# schema_v4_0.net
KiCad netlist of a schematic drawn in EAGLE
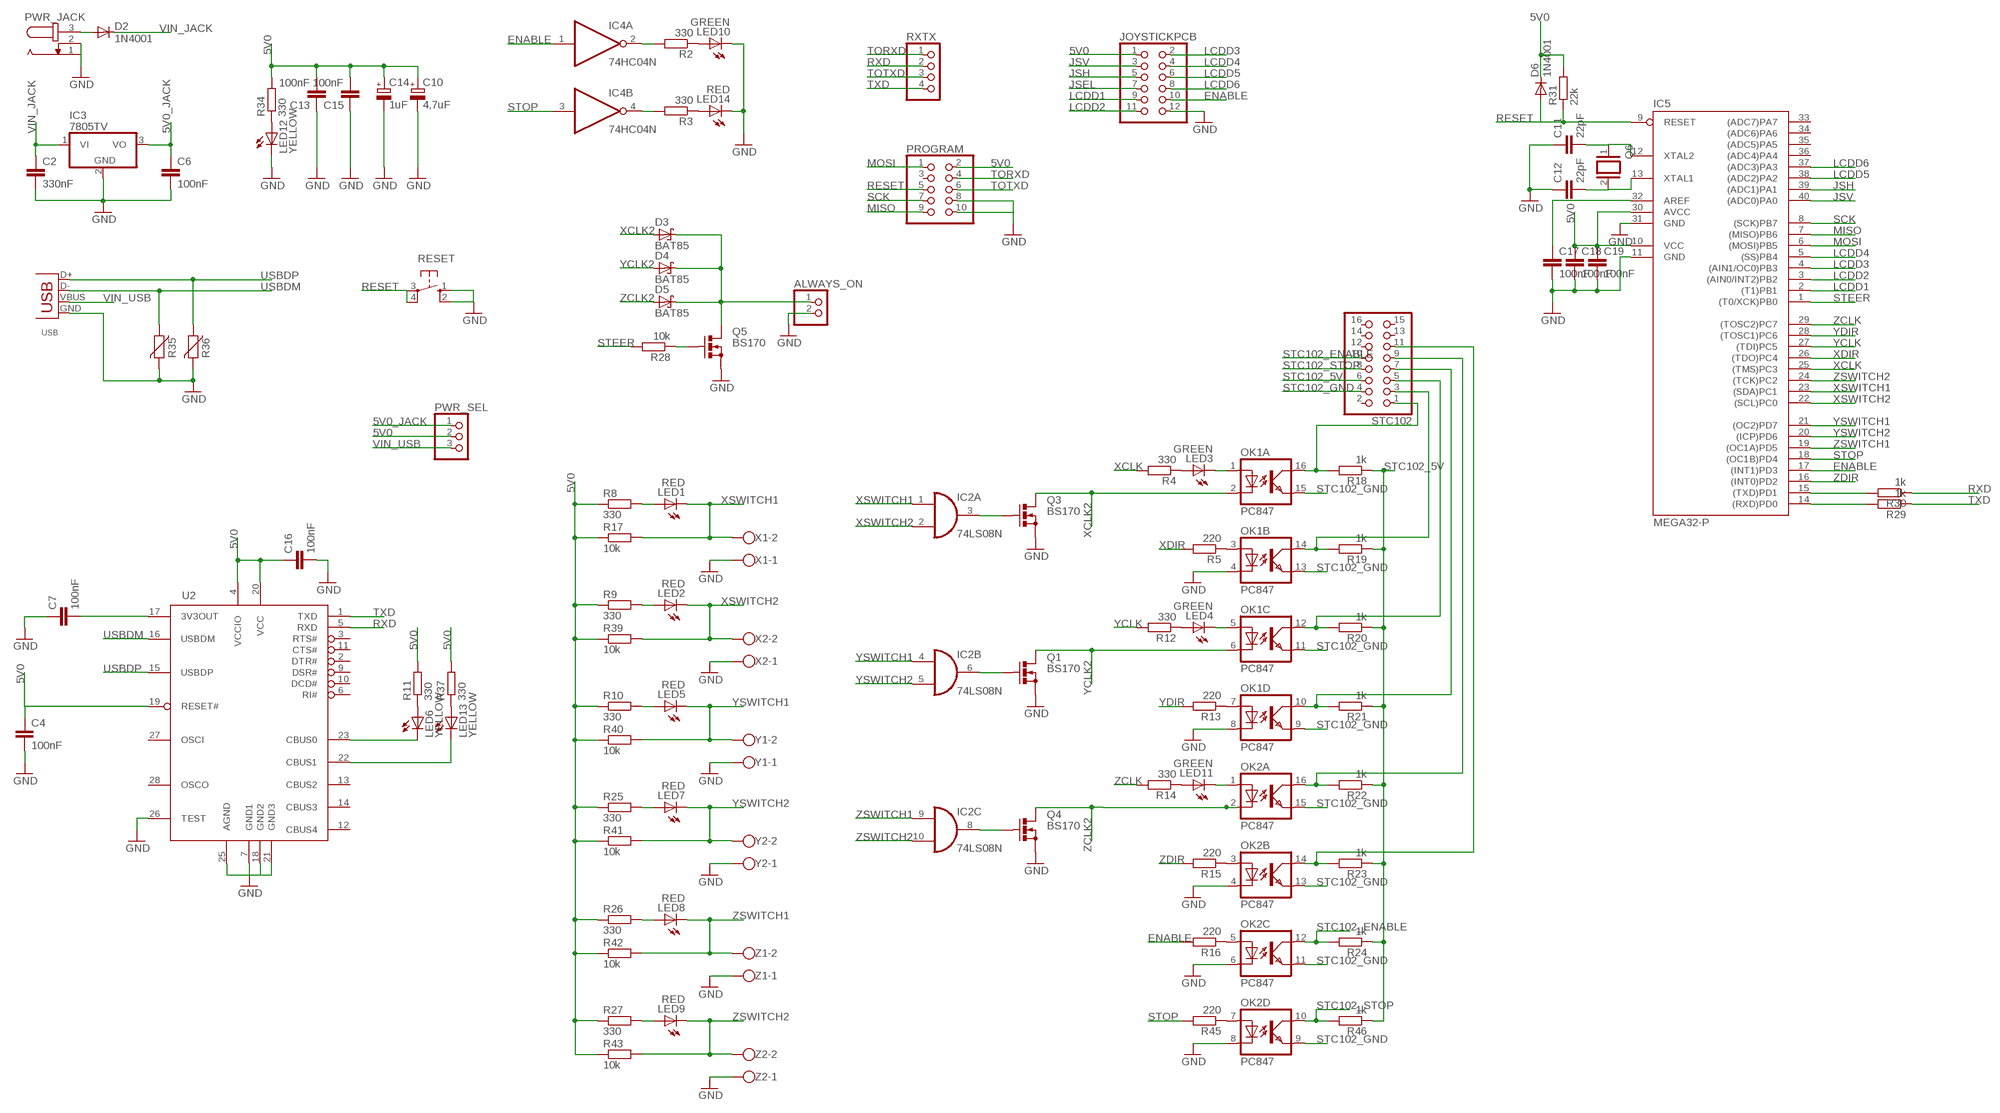
[diagram p0: schematic, sheet 1]

(export (version "E")
  (design (tool "Eeschema 10.0.6"))
  (components
    (comp (ref "ALWAYS_ON")
      (value "PINHD-1X2")
      (footprint "eagle-import:1X02")
      (libsource (lib "eagle-import") (part "PINHD-1X2"))
    )
    (comp (ref "C2")
      (value "330nF")
      (footprint "eagle-import:C025-025X050")
      (libsource (lib "eagle-import") (part "C-EU025-025X050"))
    )
    (comp (ref "C4")
      (value "100nF")
      (footprint "eagle-import:C0805K")
      (libsource (lib "eagle-import") (part "C-EUC0805K"))
    )
    (comp (ref "C6")
      (value "100nF")
      (footprint "eagle-import:C025-025X050")
      (libsource (lib "eagle-import") (part "C-EU025-025X050"))
    )
    (comp (ref "C7")
      (value "100nF")
      (footprint "eagle-import:C0805K")
      (libsource (lib "eagle-import") (part "C-EUC0805K"))
    )
    (comp (ref "C10")
      (value "4,7uF")
      (footprint "eagle-import:E2,5-5")
      (libsource (lib "eagle-import") (part "CPOL-EUE2.5-5"))
    )
    (comp (ref "C11")
      (value "22pF")
      (footprint "eagle-import:C0805K")
      (libsource (lib "eagle-import") (part "C-EUC0805K"))
    )
    (comp (ref "C12")
      (value "22pF")
      (footprint "eagle-import:C0805K")
      (libsource (lib "eagle-import") (part "C-EUC0805K"))
    )
    (comp (ref "C13")
      (value "100nF")
      (footprint "eagle-import:C025-025X050")
      (libsource (lib "eagle-import") (part "C-EU025-025X050"))
    )
    (comp (ref "C14")
      (value "1uF")
      (footprint "eagle-import:E2,5-5")
      (libsource (lib "eagle-import") (part "CPOL-EUE2.5-5"))
    )
    (comp (ref "C15")
      (value "100nF")
      (footprint "eagle-import:C025-025X050")
      (libsource (lib "eagle-import") (part "C-EU025-025X050"))
    )
    (comp (ref "C16")
      (value "100nF")
      (footprint "eagle-import:C0805K")
      (libsource (lib "eagle-import") (part "C-EUC0805K"))
    )
    (comp (ref "C17")
      (value "100nF")
      (footprint "eagle-import:C0805K")
      (libsource (lib "eagle-import") (part "C-EUC0805K"))
    )
    (comp (ref "C18")
      (value "100nF")
      (footprint "eagle-import:C0805K")
      (libsource (lib "eagle-import") (part "C-EUC0805K"))
    )
    (comp (ref "C19")
      (value "100nF")
      (footprint "eagle-import:C0805K")
      (libsource (lib "eagle-import") (part "C-EUC0805K"))
    )
    (comp (ref "D2")
      (value "1N4001")
      (footprint "eagle-import:DO41-10")
      (libsource (lib "eagle-import") (part "1N4004"))
    )
    (comp (ref "D3")
      (value "BAT85")
      (footprint "eagle-import:DO35-10")
      (libsource (lib "eagle-import") (part "BAT42"))
    )
    (comp (ref "D4")
      (value "BAT85")
      (footprint "eagle-import:DO35-10")
      (libsource (lib "eagle-import") (part "BAT42"))
    )
    (comp (ref "D5")
      (value "BAT85")
      (footprint "eagle-import:DO35-10")
      (libsource (lib "eagle-import") (part "BAT42"))
    )
    (comp (ref "D6")
      (value "1N4001")
      (footprint "eagle-import:DO41-10")
      (libsource (lib "eagle-import") (part "1N4004"))
    )
    (comp (ref "IC2")
      (value "74LS08N")
      (footprint "eagle-import:DIL14")
      (libsource (lib "eagle-import") (part "7408NLS"))
    )
    (comp (ref "IC3")
      (value "7805TV")
      (footprint "eagle-import:TO220V")
      (libsource (lib "eagle-import") (part "78TV05"))
    )
    (comp (ref "IC4")
      (value "74HC04N")
      (footprint "eagle-import:DIL14")
      (libsource (lib "eagle-import") (part "7404NHC"))
    )
    (comp (ref "IC5")
      (value "MEGA32-P")
      (footprint "eagle-import:DIL40")
      (fields (field (name "MPN") "ATMEGA32-16PU"))
      (libsource (lib "eagle-import") (part "MEGA32-P"))
    )
    (comp (ref "JOYSTICKPCB")
      (value "PINHD-2X6")
      (footprint "eagle-import:2X06")
      (libsource (lib "eagle-import") (part "PINHD-2X6"))
    )
    (comp (ref "LED1")
      (value "RED")
      (footprint "eagle-import:LED3MM")
      (libsource (lib "eagle-import") (part "LED3MM"))
    )
    (comp (ref "LED2")
      (value "RED")
      (footprint "eagle-import:LED3MM")
      (libsource (lib "eagle-import") (part "LED3MM"))
    )
    (comp (ref "LED3")
      (value "GREEN")
      (footprint "eagle-import:LED3MM")
      (libsource (lib "eagle-import") (part "LED3MM"))
    )
    (comp (ref "LED4")
      (value "GREEN")
      (footprint "eagle-import:LED3MM")
      (libsource (lib "eagle-import") (part "LED3MM"))
    )
    (comp (ref "LED5")
      (value "RED")
      (footprint "eagle-import:LED3MM")
      (libsource (lib "eagle-import") (part "LED3MM"))
    )
    (comp (ref "LED6")
      (value "YELLOW")
      (footprint "eagle-import:LED3MM")
      (libsource (lib "eagle-import") (part "LED3MM"))
    )
    (comp (ref "LED7")
      (value "RED")
      (footprint "eagle-import:LED3MM")
      (libsource (lib "eagle-import") (part "LED3MM"))
    )
    (comp (ref "LED8")
      (value "RED")
      (footprint "eagle-import:LED3MM")
      (libsource (lib "eagle-import") (part "LED3MM"))
    )
    (comp (ref "LED9")
      (value "RED")
      (footprint "eagle-import:LED3MM")
      (libsource (lib "eagle-import") (part "LED3MM"))
    )
    (comp (ref "LED10")
      (value "GREEN")
      (footprint "eagle-import:LED3MM")
      (libsource (lib "eagle-import") (part "LED3MM"))
    )
    (comp (ref "LED11")
      (value "GREEN")
      (footprint "eagle-import:LED3MM")
      (libsource (lib "eagle-import") (part "LED3MM"))
    )
    (comp (ref "LED12")
      (value "YELLOW")
      (footprint "eagle-import:LED3MM")
      (libsource (lib "eagle-import") (part "LED3MM"))
    )
    (comp (ref "LED13")
      (value "YELLOW")
      (footprint "eagle-import:LED3MM")
      (libsource (lib "eagle-import") (part "LED3MM"))
    )
    (comp (ref "LED14")
      (value "RED")
      (footprint "eagle-import:LED3MM")
      (libsource (lib "eagle-import") (part "LED3MM"))
    )
    (comp (ref "OK1")
      (value "PC847")
      (footprint "eagle-import:DIL16")
      (libsource (lib "eagle-import") (part "PC847"))
    )
    (comp (ref "OK2")
      (value "PC847")
      (footprint "eagle-import:DIL16")
      (libsource (lib "eagle-import") (part "PC847"))
    )
    (comp (ref "PROGRAM")
      (value "PINHD-2X5")
      (footprint "eagle-import:2X05")
      (libsource (lib "eagle-import") (part "PINHD-2X5"))
    )
    (comp (ref "PWR_JACK")
      (value "JACK-PLUG0")
      (footprint "eagle-import:SPC4077")
      (libsource (lib "eagle-import") (part "JACK-PLUG0"))
    )
    (comp (ref "PWR_SEL")
      (value "PINHD-1X3")
      (footprint "eagle-import:1X03")
      (libsource (lib "eagle-import") (part "PINHD-1X3"))
    )
    (comp (ref "Q1")
      (value "BS170")
      (footprint "eagle-import:SOT54E")
      (libsource (lib "eagle-import") (part "BS170"))
    )
    (comp (ref "Q3")
      (value "BS170")
      (footprint "eagle-import:SOT54E")
      (libsource (lib "eagle-import") (part "BS170"))
    )
    (comp (ref "Q4")
      (value "BS170")
      (footprint "eagle-import:SOT54E")
      (libsource (lib "eagle-import") (part "BS170"))
    )
    (comp (ref "Q5")
      (value "BS170")
      (footprint "eagle-import:SOT54E")
      (libsource (lib "eagle-import") (part "BS170"))
    )
    (comp (ref "Q6")
      (value "XTAL/S")
      (footprint "eagle-import:QS")
      (libsource (lib "eagle-import") (part "XTAL/S"))
    )
    (comp (ref "R2")
      (value "330")
      (footprint "eagle-import:0207_10")
      (libsource (lib "eagle-import") (part "R-EU_0207/10"))
    )
    (comp (ref "R3")
      (value "330")
      (footprint "eagle-import:0207_10")
      (libsource (lib "eagle-import") (part "R-EU_0207/10"))
    )
    (comp (ref "R4")
      (value "330")
      (footprint "eagle-import:0207_10")
      (libsource (lib "eagle-import") (part "R-EU_0207/10"))
    )
    (comp (ref "R5")
      (value "220")
      (footprint "eagle-import:0207_10")
      (libsource (lib "eagle-import") (part "R-EU_0207/10"))
    )
    (comp (ref "R8")
      (value "330")
      (footprint "eagle-import:R0805")
      (libsource (lib "eagle-import") (part "R-EU_R0805"))
    )
    (comp (ref "R9")
      (value "330")
      (footprint "eagle-import:R0805")
      (libsource (lib "eagle-import") (part "R-EU_R0805"))
    )
    (comp (ref "R10")
      (value "330")
      (footprint "eagle-import:R0805")
      (libsource (lib "eagle-import") (part "R-EU_R0805"))
    )
    (comp (ref "R11")
      (value "330")
      (footprint "eagle-import:R0805")
      (libsource (lib "eagle-import") (part "R-EU_R0805"))
    )
    (comp (ref "R12")
      (value "330")
      (footprint "eagle-import:0207_10")
      (libsource (lib "eagle-import") (part "R-EU_0207/10"))
    )
    (comp (ref "R13")
      (value "220")
      (footprint "eagle-import:0207_10")
      (libsource (lib "eagle-import") (part "R-EU_0207/10"))
    )
    (comp (ref "R14")
      (value "330")
      (footprint "eagle-import:0207_10")
      (libsource (lib "eagle-import") (part "R-EU_0207/10"))
    )
    (comp (ref "R15")
      (value "220")
      (footprint "eagle-import:0207_10")
      (libsource (lib "eagle-import") (part "R-EU_0207/10"))
    )
    (comp (ref "R16")
      (value "220")
      (footprint "eagle-import:0207_10")
      (libsource (lib "eagle-import") (part "R-EU_0207/10"))
    )
    (comp (ref "R17")
      (value "10k")
      (footprint "eagle-import:0207_10")
      (libsource (lib "eagle-import") (part "R-EU_0207/10"))
    )
    (comp (ref "R18")
      (value "1k")
      (footprint "eagle-import:0207_10")
      (libsource (lib "eagle-import") (part "R-EU_0207/10"))
    )
    (comp (ref "R19")
      (value "1k")
      (footprint "eagle-import:0207_10")
      (libsource (lib "eagle-import") (part "R-EU_0207/10"))
    )
    (comp (ref "R20")
      (value "1k")
      (footprint "eagle-import:0207_10")
      (libsource (lib "eagle-import") (part "R-EU_0207/10"))
    )
    (comp (ref "R21")
      (value "1k")
      (footprint "eagle-import:0207_10")
      (libsource (lib "eagle-import") (part "R-EU_0207/10"))
    )
    (comp (ref "R22")
      (value "1k")
      (footprint "eagle-import:0207_10")
      (libsource (lib "eagle-import") (part "R-EU_0207/10"))
    )
    (comp (ref "R23")
      (value "1k")
      (footprint "eagle-import:0207_10")
      (libsource (lib "eagle-import") (part "R-EU_0207/10"))
    )
    (comp (ref "R24")
      (value "1k")
      (footprint "eagle-import:0207_10")
      (libsource (lib "eagle-import") (part "R-EU_0207/10"))
    )
    (comp (ref "R25")
      (value "330")
      (footprint "eagle-import:R0805")
      (libsource (lib "eagle-import") (part "R-EU_R0805"))
    )
    (comp (ref "R26")
      (value "330")
      (footprint "eagle-import:R0805")
      (libsource (lib "eagle-import") (part "R-EU_R0805"))
    )
    (comp (ref "R27")
      (value "330")
      (footprint "eagle-import:R0805")
      (libsource (lib "eagle-import") (part "R-EU_R0805"))
    )
    (comp (ref "R28")
      (value "10k")
      (footprint "eagle-import:0207_10")
      (libsource (lib "eagle-import") (part "R-EU_0207/10"))
    )
    (comp (ref "R29")
      (value "1k")
      (footprint "eagle-import:R0805")
      (libsource (lib "eagle-import") (part "R-EU_R0805"))
    )
    (comp (ref "R30")
      (value "1k")
      (footprint "eagle-import:R0805")
      (libsource (lib "eagle-import") (part "R-EU_R0805"))
    )
    (comp (ref "R31")
      (value "22k")
      (footprint "eagle-import:0207_10")
      (libsource (lib "eagle-import") (part "R-EU_0207/10"))
    )
    (comp (ref "R34")
      (value "330")
      (footprint "eagle-import:0207_10")
      (libsource (lib "eagle-import") (part "R-EU_0207/10"))
    )
    (comp (ref "R35")
      (value "VARISTORCN0603")
      (footprint "eagle-import:CT_CN0603")
      (libsource (lib "eagle-import") (part "VARISTORCN0603"))
    )
    (comp (ref "R36")
      (value "VARISTORCN0603")
      (footprint "eagle-import:CT_CN0603")
      (libsource (lib "eagle-import") (part "VARISTORCN0603"))
    )
    (comp (ref "R37")
      (value "330")
      (footprint "eagle-import:R0805")
      (libsource (lib "eagle-import") (part "R-EU_R0805"))
    )
    (comp (ref "R39")
      (value "10k")
      (footprint "eagle-import:0207_10")
      (libsource (lib "eagle-import") (part "R-EU_0207/10"))
    )
    (comp (ref "R40")
      (value "10k")
      (footprint "eagle-import:0207_10")
      (libsource (lib "eagle-import") (part "R-EU_0207/10"))
    )
    (comp (ref "R41")
      (value "10k")
      (footprint "eagle-import:0207_10")
      (libsource (lib "eagle-import") (part "R-EU_0207/10"))
    )
    (comp (ref "R42")
      (value "10k")
      (footprint "eagle-import:0207_10")
      (libsource (lib "eagle-import") (part "R-EU_0207/10"))
    )
    (comp (ref "R43")
      (value "10k")
      (footprint "eagle-import:0207_10")
      (libsource (lib "eagle-import") (part "R-EU_0207/10"))
    )
    (comp (ref "R45")
      (value "220")
      (footprint "eagle-import:0207_10")
      (libsource (lib "eagle-import") (part "R-EU_0207/10"))
    )
    (comp (ref "R46")
      (value "1k")
      (footprint "eagle-import:0207_10")
      (libsource (lib "eagle-import") (part "R-EU_0207/10"))
    )
    (comp (ref "RESET")
      (value "10-XX")
      (footprint "eagle-import:B3F-10XX")
      (fields (field (name "MPN") "B3F-1000"))
      (libsource (lib "eagle-import") (part "10-XX"))
    )
    (comp (ref "RXTX")
      (value "PINHD-1X4")
      (footprint "eagle-import:1X04")
      (libsource (lib "eagle-import") (part "PINHD-1X4"))
    )
    (comp (ref "STC102")
      (value "PINHD-2X8")
      (footprint "eagle-import:2X08")
      (libsource (lib "eagle-import") (part "PINHD-2X8"))
    )
    (comp (ref "U2")
      (value "FT232RL")
      (footprint "eagle-import:SSOP28DB")
      (libsource (lib "eagle-import") (part "FT232RL"))
    )
    (comp (ref "USB")
      (value "USB-B-H")
      (footprint "eagle-import:USB-B-H")
      (libsource (lib "eagle-import") (part "USB-B-H"))
    )
    (comp (ref "X1")
      (value "W237-102")
      (footprint "eagle-import:W237-102")
      (fields (field (name "MPN") "237-102"))
      (libsource (lib "eagle-import") (part "W237-102"))
    )
    (comp (ref "X2")
      (value "W237-102")
      (footprint "eagle-import:W237-102")
      (fields (field (name "MPN") "237-102"))
      (libsource (lib "eagle-import") (part "W237-102"))
    )
    (comp (ref "Y1")
      (value "W237-102")
      (footprint "eagle-import:W237-102")
      (fields (field (name "MPN") "237-102"))
      (libsource (lib "eagle-import") (part "W237-102"))
    )
    (comp (ref "Y2")
      (value "W237-102")
      (footprint "eagle-import:W237-102")
      (fields (field (name "MPN") "237-102"))
      (libsource (lib "eagle-import") (part "W237-102"))
    )
    (comp (ref "Z1")
      (value "W237-102")
      (footprint "eagle-import:W237-102")
      (fields (field (name "MPN") "237-102"))
      (libsource (lib "eagle-import") (part "W237-102"))
    )
    (comp (ref "Z2")
      (value "W237-102")
      (footprint "eagle-import:W237-102")
      (fields (field (name "MPN") "237-102"))
      (libsource (lib "eagle-import") (part "W237-102"))
    )
  )
  (nets
    (net (code "1") (name "/5V0") (class "Default")
      (node (ref "C10") (pin "+") (pinfunction "+_+") (pintype "passive"))
      (node (ref "C13") (pin "2") (pinfunction "2_2") (pintype "passive"))
      (node (ref "C14") (pin "+") (pinfunction "+_+") (pintype "passive"))
      (node (ref "C15") (pin "2") (pinfunction "2_2") (pintype "passive"))
      (node (ref "C16") (pin "1") (pinfunction "1_1") (pintype "passive"))
      (node (ref "C18") (pin "1") (pinfunction "1_1") (pintype "passive"))
      (node (ref "C19") (pin "1") (pinfunction "1_1") (pintype "passive"))
      (node (ref "C4") (pin "1") (pinfunction "1_1") (pintype "passive"))
      (node (ref "D6") (pin "C") (pinfunction "C_C") (pintype "passive"))
      (node (ref "IC5") (pin "10") (pinfunction "VCC_10") (pintype "power_in"))
      (node (ref "IC5") (pin "30") (pinfunction "AVCC_30") (pintype "power_in"))
      (node (ref "JOYSTICKPCB") (pin "1") (pinfunction "1_1") (pintype "passive"))
      (node (ref "PROGRAM") (pin "2") (pinfunction "2_2") (pintype "passive"))
      (node (ref "PWR_SEL") (pin "2") (pinfunction "2_2") (pintype "passive"))
      (node (ref "R10") (pin "1") (pinfunction "1_1") (pintype "passive"))
      (node (ref "R11") (pin "2") (pinfunction "2_2") (pintype "passive"))
      (node (ref "R17") (pin "1") (pinfunction "1_1") (pintype "passive"))
      (node (ref "R25") (pin "1") (pinfunction "1_1") (pintype "passive"))
      (node (ref "R26") (pin "1") (pinfunction "1_1") (pintype "passive"))
      (node (ref "R27") (pin "1") (pinfunction "1_1") (pintype "passive"))
      (node (ref "R31") (pin "2") (pinfunction "2_2") (pintype "passive"))
      (node (ref "R34") (pin "2") (pinfunction "2_2") (pintype "passive"))
      (node (ref "R37") (pin "2") (pinfunction "2_2") (pintype "passive"))
      (node (ref "R39") (pin "1") (pinfunction "1_1") (pintype "passive"))
      (node (ref "R40") (pin "1") (pinfunction "1_1") (pintype "passive"))
      (node (ref "R41") (pin "1") (pinfunction "1_1") (pintype "passive"))
      (node (ref "R42") (pin "1") (pinfunction "1_1") (pintype "passive"))
      (node (ref "R43") (pin "1") (pinfunction "1_1") (pintype "passive"))
      (node (ref "R8") (pin "1") (pinfunction "1_1") (pintype "passive"))
      (node (ref "R9") (pin "1") (pinfunction "1_1") (pintype "passive"))
      (node (ref "U2") (pin "19") (pinfunction "RESET#_19") (pintype "input"))
      (node (ref "U2") (pin "20") (pinfunction "VCC_20") (pintype "power_in"))
      (node (ref "U2") (pin "4") (pinfunction "VCCIO_4") (pintype "power_in"))
    )
    (net (code "2") (name "/5V0_JACK") (class "Default")
      (node (ref "C6") (pin "1") (pinfunction "1_1") (pintype "passive"))
      (node (ref "IC3") (pin "3") (pinfunction "VO_3") (pintype "passive"))
      (node (ref "PWR_SEL") (pin "1") (pinfunction "1_1") (pintype "passive"))
    )
    (net (code "3") (name "/ENABLE") (class "Default")
      (node (ref "IC4") (pin "1") (pinfunction "I_1") (pintype "input"))
      (node (ref "IC5") (pin "17") (pinfunction "(INT1)PD3_17") (pintype "bidirectional"))
      (node (ref "JOYSTICKPCB") (pin "10") (pinfunction "10_10") (pintype "passive"))
      (node (ref "R16") (pin "2") (pinfunction "2_2") (pintype "passive"))
    )
    (net (code "4") (name "/JSEL") (class "Default")
      (node (ref "JOYSTICKPCB") (pin "7") (pinfunction "7_7") (pintype "passive"))
    )
    (net (code "5") (name "/JSH") (class "Default")
      (node (ref "IC5") (pin "39") (pinfunction "(ADC1)PA1_39") (pintype "bidirectional"))
      (node (ref "JOYSTICKPCB") (pin "5") (pinfunction "5_5") (pintype "passive"))
    )
    (net (code "6") (name "/JSV") (class "Default")
      (node (ref "IC5") (pin "40") (pinfunction "(ADC0)PA0_40") (pintype "bidirectional"))
      (node (ref "JOYSTICKPCB") (pin "3") (pinfunction "3_3") (pintype "passive"))
    )
    (net (code "7") (name "/LCDD1") (class "Default")
      (node (ref "IC5") (pin "2") (pinfunction "(T1)PB1_2") (pintype "bidirectional"))
      (node (ref "JOYSTICKPCB") (pin "9") (pinfunction "9_9") (pintype "passive"))
    )
    (net (code "8") (name "/LCDD2") (class "Default")
      (node (ref "IC5") (pin "3") (pinfunction "(AIN0/INT2)PB2_3") (pintype "bidirectional"))
      (node (ref "JOYSTICKPCB") (pin "11") (pinfunction "11_11") (pintype "passive"))
    )
    (net (code "9") (name "/LCDD3") (class "Default")
      (node (ref "IC5") (pin "4") (pinfunction "(AIN1/OC0)PB3_4") (pintype "bidirectional"))
      (node (ref "JOYSTICKPCB") (pin "2") (pinfunction "2_2") (pintype "passive"))
    )
    (net (code "10") (name "/LCDD4") (class "Default")
      (node (ref "IC5") (pin "5") (pinfunction "(SS)PB4_5") (pintype "bidirectional"))
      (node (ref "JOYSTICKPCB") (pin "4") (pinfunction "4_4") (pintype "passive"))
    )
    (net (code "11") (name "/LCDD5") (class "Default")
      (node (ref "IC5") (pin "38") (pinfunction "(ADC2)PA2_38") (pintype "bidirectional"))
      (node (ref "JOYSTICKPCB") (pin "6") (pinfunction "6_6") (pintype "passive"))
    )
    (net (code "12") (name "/LCDD6") (class "Default")
      (node (ref "IC5") (pin "37") (pinfunction "(ADC3)PA3_37") (pintype "bidirectional"))
      (node (ref "JOYSTICKPCB") (pin "8") (pinfunction "8_8") (pintype "passive"))
    )
    (net (code "13") (name "/MISO") (class "Default")
      (node (ref "IC5") (pin "7") (pinfunction "(MISO)PB6_7") (pintype "bidirectional"))
      (node (ref "PROGRAM") (pin "9") (pinfunction "9_9") (pintype "passive"))
    )
    (net (code "14") (name "/MOSI") (class "Default")
      (node (ref "IC5") (pin "6") (pinfunction "(MOSI)PB5_6") (pintype "bidirectional"))
      (node (ref "PROGRAM") (pin "1") (pinfunction "1_1") (pintype "passive"))
    )
    (net (code "15") (name "/RESET") (class "Default")
      (node (ref "D6") (pin "A") (pinfunction "A_A") (pintype "passive"))
      (node (ref "IC5") (pin "9") (pinfunction "RESET_9") (pintype "input"))
      (node (ref "PROGRAM") (pin "5") (pinfunction "5_5") (pintype "passive"))
      (node (ref "R31") (pin "1") (pinfunction "1_1") (pintype "passive"))
      (node (ref "RESET") (pin "3") (pinfunction "P_3") (pintype "passive"))
      (node (ref "RESET") (pin "4") (pinfunction "P1_4") (pintype "passive"))
    )
    (net (code "16") (name "/RXD") (class "Default")
      (node (ref "R30") (pin "1") (pinfunction "1_1") (pintype "passive"))
      (node (ref "RXTX") (pin "2") (pinfunction "2_2") (pintype "passive"))
      (node (ref "U2") (pin "5") (pinfunction "RXD_5") (pintype "input"))
    )
    (net (code "17") (name "/SCK") (class "Default")
      (node (ref "IC5") (pin "8") (pinfunction "(SCK)PB7_8") (pintype "bidirectional"))
      (node (ref "PROGRAM") (pin "7") (pinfunction "7_7") (pintype "passive"))
    )
    (net (code "18") (name "/STC102_5V") (class "Default")
      (node (ref "R18") (pin "1") (pinfunction "1_1") (pintype "passive"))
      (node (ref "R19") (pin "1") (pinfunction "1_1") (pintype "passive"))
      (node (ref "R20") (pin "1") (pinfunction "1_1") (pintype "passive"))
      (node (ref "R21") (pin "1") (pinfunction "1_1") (pintype "passive"))
      (node (ref "R22") (pin "1") (pinfunction "1_1") (pintype "passive"))
      (node (ref "R23") (pin "1") (pinfunction "1_1") (pintype "passive"))
      (node (ref "R24") (pin "1") (pinfunction "1_1") (pintype "passive"))
      (node (ref "R46") (pin "1") (pinfunction "1_1") (pintype "passive"))
      (node (ref "STC102") (pin "6") (pinfunction "6_6") (pintype "passive"))
    )
    (net (code "19") (name "/STC102_ENABLE") (class "Default")
      (node (ref "OK2") (pin "12") (pinfunction "COL_12") (pintype "passive"))
      (node (ref "R24") (pin "2") (pinfunction "2_2") (pintype "passive"))
      (node (ref "STC102") (pin "10") (pinfunction "10_10") (pintype "passive"))
    )
    (net (code "20") (name "/STC102_GND") (class "Default")
      (node (ref "OK1") (pin "11") (pinfunction "EMIT_11") (pintype "passive"))
      (node (ref "OK1") (pin "13") (pinfunction "EMIT_13") (pintype "passive"))
      (node (ref "OK1") (pin "15") (pinfunction "EMIT_15") (pintype "passive"))
      (node (ref "OK1") (pin "9") (pinfunction "EMIT_9") (pintype "passive"))
      (node (ref "OK2") (pin "11") (pinfunction "EMIT_11") (pintype "passive"))
      (node (ref "OK2") (pin "13") (pinfunction "EMIT_13") (pintype "passive"))
      (node (ref "OK2") (pin "15") (pinfunction "EMIT_15") (pintype "passive"))
      (node (ref "OK2") (pin "9") (pinfunction "EMIT_9") (pintype "passive"))
      (node (ref "STC102") (pin "4") (pinfunction "4_4") (pintype "passive"))
    )
    (net (code "21") (name "/STC102_STOP") (class "Default")
      (node (ref "OK2") (pin "10") (pinfunction "COL_10") (pintype "passive"))
      (node (ref "R46") (pin "2") (pinfunction "2_2") (pintype "passive"))
      (node (ref "STC102") (pin "8") (pinfunction "8_8") (pintype "passive"))
    )
    (net (code "22") (name "/STEER") (class "Default")
      (node (ref "IC5") (pin "1") (pinfunction "(T0/XCK)PB0_1") (pintype "bidirectional"))
      (node (ref "R28") (pin "2") (pinfunction "2_2") (pintype "passive"))
    )
    (net (code "23") (name "/STOP") (class "Default")
      (node (ref "IC4") (pin "3") (pinfunction "I_3") (pintype "input"))
      (node (ref "IC5") (pin "18") (pinfunction "(OC1B)PD4_18") (pintype "bidirectional"))
      (node (ref "R45") (pin "2") (pinfunction "2_2") (pintype "passive"))
    )
    (net (code "24") (name "/TORXD") (class "Default")
      (node (ref "PROGRAM") (pin "4") (pinfunction "4_4") (pintype "passive"))
      (node (ref "RXTX") (pin "1") (pinfunction "1_1") (pintype "passive"))
    )
    (net (code "25") (name "/TOTXD") (class "Default")
      (node (ref "PROGRAM") (pin "6") (pinfunction "6_6") (pintype "passive"))
      (node (ref "RXTX") (pin "3") (pinfunction "3_3") (pintype "passive"))
    )
    (net (code "26") (name "/TXD") (class "Default")
      (node (ref "R29") (pin "1") (pinfunction "1_1") (pintype "passive"))
      (node (ref "RXTX") (pin "4") (pinfunction "4_4") (pintype "passive"))
      (node (ref "U2") (pin "1") (pinfunction "TXD_1") (pintype "output"))
    )
    (net (code "27") (name "/USBDM") (class "Default")
      (node (ref "R35") (pin "1") (pinfunction "1_1") (pintype "passive"))
      (node (ref "U2") (pin "16") (pinfunction "USBDM_16") (pintype "bidirectional"))
      (node (ref "USB") (pin "D-") (pinfunction "D-_D-") (pintype "bidirectional"))
    )
    (net (code "28") (name "/USBDP") (class "Default")
      (node (ref "R36") (pin "1") (pinfunction "1_1") (pintype "passive"))
      (node (ref "U2") (pin "15") (pinfunction "USBDP_15") (pintype "bidirectional"))
      (node (ref "USB") (pin "D+") (pinfunction "D+_D+") (pintype "bidirectional"))
    )
    (net (code "29") (name "/VIN_JACK") (class "Default")
      (node (ref "C2") (pin "1") (pinfunction "1_1") (pintype "passive"))
      (node (ref "D2") (pin "C") (pinfunction "C_C") (pintype "passive"))
      (node (ref "IC3") (pin "1") (pinfunction "VI_1") (pintype "input"))
    )
    (net (code "30") (name "/VIN_USB") (class "Default")
      (node (ref "PWR_SEL") (pin "3") (pinfunction "3_3") (pintype "passive"))
      (node (ref "USB") (pin "VBUS") (pinfunction "VBUS_VBUS") (pintype "bidirectional"))
    )
    (net (code "31") (name "/XCLK") (class "Default")
      (node (ref "IC5") (pin "25") (pinfunction "(TMS)PC3_25") (pintype "bidirectional"))
      (node (ref "R4") (pin "2") (pinfunction "2_2") (pintype "passive"))
    )
    (net (code "32") (name "/XCLK2") (class "Default")
      (node (ref "D3") (pin "A") (pinfunction "A_A") (pintype "passive"))
      (node (ref "OK1") (pin "2") (pinfunction "C_2") (pintype "passive"))
      (node (ref "Q3") (pin "D") (pinfunction "D_D") (pintype "passive"))
    )
    (net (code "33") (name "/XDIR") (class "Default")
      (node (ref "IC5") (pin "26") (pinfunction "(TDO)PC4_26") (pintype "bidirectional"))
      (node (ref "R5") (pin "2") (pinfunction "2_2") (pintype "passive"))
    )
    (net (code "34") (name "/XSWITCH1") (class "Default")
      (node (ref "IC2") (pin "1") (pinfunction "I0_1") (pintype "input"))
      (node (ref "IC5") (pin "23") (pinfunction "(SDA)PC1_23") (pintype "bidirectional"))
      (node (ref "LED1") (pin "K") (pinfunction "C_K") (pintype "passive"))
      (node (ref "R17") (pin "2") (pinfunction "2_2") (pintype "passive"))
      (node (ref "X1") (pin "2") (pinfunction "KL_2") (pintype "passive"))
    )
    (net (code "35") (name "/XSWITCH2") (class "Default")
      (node (ref "IC2") (pin "2") (pinfunction "I1_2") (pintype "input"))
      (node (ref "IC5") (pin "22") (pinfunction "(SCL)PC0_22") (pintype "bidirectional"))
      (node (ref "LED2") (pin "K") (pinfunction "C_K") (pintype "passive"))
      (node (ref "R39") (pin "2") (pinfunction "2_2") (pintype "passive"))
      (node (ref "X2") (pin "2") (pinfunction "KL_2") (pintype "passive"))
    )
    (net (code "36") (name "/YCLK") (class "Default")
      (node (ref "IC5") (pin "27") (pinfunction "(TDI)PC5_27") (pintype "bidirectional"))
      (node (ref "R12") (pin "2") (pinfunction "2_2") (pintype "passive"))
    )
    (net (code "37") (name "/YCLK2") (class "Default")
      (node (ref "D4") (pin "A") (pinfunction "A_A") (pintype "passive"))
      (node (ref "OK1") (pin "6") (pinfunction "C_6") (pintype "passive"))
      (node (ref "Q1") (pin "D") (pinfunction "D_D") (pintype "passive"))
    )
    (net (code "38") (name "/YDIR") (class "Default")
      (node (ref "IC5") (pin "28") (pinfunction "(TOSC1)PC6_28") (pintype "bidirectional"))
      (node (ref "R13") (pin "2") (pinfunction "2_2") (pintype "passive"))
    )
    (net (code "39") (name "/YSWITCH1") (class "Default")
      (node (ref "IC2") (pin "4") (pinfunction "I0_4") (pintype "input"))
      (node (ref "IC5") (pin "21") (pinfunction "(OC2)PD7_21") (pintype "bidirectional"))
      (node (ref "LED5") (pin "K") (pinfunction "C_K") (pintype "passive"))
      (node (ref "R40") (pin "2") (pinfunction "2_2") (pintype "passive"))
      (node (ref "Y1") (pin "2") (pinfunction "KL_2") (pintype "passive"))
    )
    (net (code "40") (name "/YSWITCH2") (class "Default")
      (node (ref "IC2") (pin "5") (pinfunction "I1_5") (pintype "input"))
      (node (ref "IC5") (pin "20") (pinfunction "(ICP)PD6_20") (pintype "bidirectional"))
      (node (ref "LED7") (pin "K") (pinfunction "C_K") (pintype "passive"))
      (node (ref "R41") (pin "2") (pinfunction "2_2") (pintype "passive"))
      (node (ref "Y2") (pin "2") (pinfunction "KL_2") (pintype "passive"))
    )
    (net (code "41") (name "/ZCLK") (class "Default")
      (node (ref "IC5") (pin "29") (pinfunction "(TOSC2)PC7_29") (pintype "bidirectional"))
      (node (ref "R14") (pin "2") (pinfunction "2_2") (pintype "passive"))
    )
    (net (code "42") (name "/ZCLK2") (class "Default")
      (node (ref "D5") (pin "A") (pinfunction "A_A") (pintype "passive"))
      (node (ref "OK2") (pin "2") (pinfunction "C_2") (pintype "passive"))
      (node (ref "Q4") (pin "D") (pinfunction "D_D") (pintype "passive"))
    )
    (net (code "43") (name "/ZDIR") (class "Default")
      (node (ref "IC5") (pin "16") (pinfunction "(INT0)PD2_16") (pintype "bidirectional"))
      (node (ref "R15") (pin "2") (pinfunction "2_2") (pintype "passive"))
    )
    (net (code "44") (name "/ZSWITCH1") (class "Default")
      (node (ref "IC2") (pin "9") (pinfunction "I0_9") (pintype "input"))
      (node (ref "IC5") (pin "19") (pinfunction "(OC1A)PD5_19") (pintype "bidirectional"))
      (node (ref "LED8") (pin "K") (pinfunction "C_K") (pintype "passive"))
      (node (ref "R42") (pin "2") (pinfunction "2_2") (pintype "passive"))
      (node (ref "Z1") (pin "2") (pinfunction "KL_2") (pintype "passive"))
    )
    (net (code "45") (name "/ZSWITCH2") (class "Default")
      (node (ref "IC2") (pin "10") (pinfunction "I1_10") (pintype "input"))
      (node (ref "IC5") (pin "24") (pinfunction "(TCK)PC2_24") (pintype "bidirectional"))
      (node (ref "LED9") (pin "K") (pinfunction "C_K") (pintype "passive"))
      (node (ref "R43") (pin "2") (pinfunction "2_2") (pintype "passive"))
      (node (ref "Z2") (pin "2") (pinfunction "KL_2") (pintype "passive"))
    )
    (net (code "46") (name "GND") (class "Default")
      (node (ref "ALWAYS_ON") (pin "2") (pinfunction "2_2") (pintype "passive"))
      (node (ref "C10") (pin "-") (pinfunction "-_-") (pintype "passive"))
      (node (ref "C11") (pin "1") (pinfunction "1_1") (pintype "passive"))
      (node (ref "C12") (pin "1") (pinfunction "1_1") (pintype "passive"))
      (node (ref "C13") (pin "1") (pinfunction "1_1") (pintype "passive"))
      (node (ref "C14") (pin "-") (pinfunction "-_-") (pintype "passive"))
      (node (ref "C15") (pin "1") (pinfunction "1_1") (pintype "passive"))
      (node (ref "C16") (pin "2") (pinfunction "2_2") (pintype "passive"))
      (node (ref "C17") (pin "2") (pinfunction "2_2") (pintype "passive"))
      (node (ref "C18") (pin "2") (pinfunction "2_2") (pintype "passive"))
      (node (ref "C19") (pin "2") (pinfunction "2_2") (pintype "passive"))
      (node (ref "C2") (pin "2") (pinfunction "2_2") (pintype "passive"))
      (node (ref "C4") (pin "2") (pinfunction "2_2") (pintype "passive"))
      (node (ref "C6") (pin "2") (pinfunction "2_2") (pintype "passive"))
      (node (ref "C7") (pin "1") (pinfunction "1_1") (pintype "passive"))
      (node (ref "IC3") (pin "2") (pinfunction "GND_2") (pintype "passive"))
      (node (ref "IC5") (pin "11") (pinfunction "GND_11") (pintype "power_in"))
      (node (ref "IC5") (pin "31") (pinfunction "GND_31") (pintype "power_in"))
      (node (ref "JOYSTICKPCB") (pin "12") (pinfunction "12_12") (pintype "passive"))
      (node (ref "LED10") (pin "K") (pinfunction "C_K") (pintype "passive"))
      (node (ref "LED12") (pin "K") (pinfunction "C_K") (pintype "passive"))
      (node (ref "LED14") (pin "K") (pinfunction "C_K") (pintype "passive"))
      (node (ref "OK1") (pin "4") (pinfunction "C_4") (pintype "passive"))
      (node (ref "OK1") (pin "8") (pinfunction "C_8") (pintype "passive"))
      (node (ref "OK2") (pin "4") (pinfunction "C_4") (pintype "passive"))
      (node (ref "OK2") (pin "6") (pinfunction "C_6") (pintype "passive"))
      (node (ref "OK2") (pin "8") (pinfunction "C_8") (pintype "passive"))
      (node (ref "PROGRAM") (pin "8") (pinfunction "8_8") (pintype "passive"))
      (node (ref "PWR_JACK") (pin "1") (pinfunction "1_1") (pintype "passive"))
      (node (ref "PWR_JACK") (pin "2") (pinfunction "2_2") (pintype "passive"))
      (node (ref "Q1") (pin "S") (pinfunction "S_S") (pintype "passive"))
      (node (ref "Q3") (pin "S") (pinfunction "S_S") (pintype "passive"))
      (node (ref "Q4") (pin "S") (pinfunction "S_S") (pintype "passive"))
      (node (ref "Q5") (pin "S") (pinfunction "S_S") (pintype "passive"))
      (node (ref "R35") (pin "2") (pinfunction "2_2") (pintype "passive"))
      (node (ref "R36") (pin "2") (pinfunction "2_2") (pintype "passive"))
      (node (ref "RESET") (pin "1") (pinfunction "S_1") (pintype "passive"))
      (node (ref "RESET") (pin "2") (pinfunction "S1_2") (pintype "passive"))
      (node (ref "U2") (pin "18") (pinfunction "GND2_18") (pintype "power_in"))
      (node (ref "U2") (pin "21") (pinfunction "GND3_21") (pintype "power_in"))
      (node (ref "U2") (pin "25") (pinfunction "AGND_25") (pintype "power_in"))
      (node (ref "U2") (pin "26") (pinfunction "TEST_26") (pintype "input"))
      (node (ref "U2") (pin "7") (pinfunction "GND1_7") (pintype "power_in"))
      (node (ref "USB") (pin "GND") (pinfunction "GND_GND") (pintype "bidirectional"))
      (node (ref "X1") (pin "1") (pinfunction "KL_1") (pintype "passive"))
      (node (ref "X2") (pin "1") (pinfunction "KL_1") (pintype "passive"))
      (node (ref "Y1") (pin "1") (pinfunction "KL_1") (pintype "passive"))
      (node (ref "Y2") (pin "1") (pinfunction "KL_1") (pintype "passive"))
      (node (ref "Z1") (pin "1") (pinfunction "KL_1") (pintype "passive"))
      (node (ref "Z2") (pin "1") (pinfunction "KL_1") (pintype "passive"))
    )
    (net (code "47") (name "Net-(ALWAYS_ON-Pad1)") (class "Default")
      (node (ref "ALWAYS_ON") (pin "1") (pinfunction "1_1") (pintype "passive"))
      (node (ref "D3") (pin "C") (pinfunction "C_C") (pintype "passive"))
      (node (ref "D4") (pin "C") (pinfunction "C_C") (pintype "passive"))
      (node (ref "D5") (pin "C") (pinfunction "C_C") (pintype "passive"))
      (node (ref "Q5") (pin "D") (pinfunction "D_D") (pintype "passive"))
    )
    (net (code "48") (name "Net-(D2-PadA)") (class "Default")
      (node (ref "D2") (pin "A") (pinfunction "A_A") (pintype "passive"))
      (node (ref "PWR_JACK") (pin "3") (pinfunction "3_3") (pintype "passive"))
    )
    (net (code "49") (name "Net-(IC2A-O)") (class "Default")
      (node (ref "IC2") (pin "3") (pinfunction "O_3") (pintype "output"))
      (node (ref "Q3") (pin "G") (pinfunction "G_G") (pintype "passive"))
    )
    (net (code "50") (name "Net-(IC2B-O)") (class "Default")
      (node (ref "IC2") (pin "6") (pinfunction "O_6") (pintype "output"))
      (node (ref "Q1") (pin "G") (pinfunction "G_G") (pintype "passive"))
    )
    (net (code "51") (name "Net-(IC2C-O)") (class "Default")
      (node (ref "IC2") (pin "8") (pinfunction "O_8") (pintype "output"))
      (node (ref "Q4") (pin "G") (pinfunction "G_G") (pintype "passive"))
    )
    (net (code "52") (name "Net-(IC4A-O)") (class "Default")
      (node (ref "IC4") (pin "2") (pinfunction "O_2") (pintype "output"))
      (node (ref "R2") (pin "2") (pinfunction "2_2") (pintype "passive"))
    )
    (net (code "53") (name "Net-(IC4B-O)") (class "Default")
      (node (ref "IC4") (pin "4") (pinfunction "O_4") (pintype "output"))
      (node (ref "R3") (pin "2") (pinfunction "2_2") (pintype "passive"))
    )
    (net (code "54") (name "Net-(IC5-(RXD)PD0)") (class "Default")
      (node (ref "IC5") (pin "14") (pinfunction "(RXD)PD0_14") (pintype "bidirectional"))
      (node (ref "R29") (pin "2") (pinfunction "2_2") (pintype "passive"))
    )
    (net (code "55") (name "Net-(IC5-(TXD)PD1)") (class "Default")
      (node (ref "IC5") (pin "15") (pinfunction "(TXD)PD1_15") (pintype "bidirectional"))
      (node (ref "R30") (pin "2") (pinfunction "2_2") (pintype "passive"))
    )
    (net (code "56") (name "Net-(IC5-AREF)") (class "Default")
      (node (ref "C17") (pin "1") (pinfunction "1_1") (pintype "passive"))
      (node (ref "IC5") (pin "32") (pinfunction "AREF_32") (pintype "passive"))
    )
    (net (code "57") (name "Net-(IC5-XTAL1)") (class "Default")
      (node (ref "C12") (pin "2") (pinfunction "2_2") (pintype "passive"))
      (node (ref "IC5") (pin "13") (pinfunction "XTAL1_13") (pintype "bidirectional"))
      (node (ref "Q6") (pin "2") (pinfunction "2_2") (pintype "passive"))
    )
    (net (code "58") (name "Net-(IC5-XTAL2)") (class "Default")
      (node (ref "C11") (pin "2") (pinfunction "2_2") (pintype "passive"))
      (node (ref "IC5") (pin "12") (pinfunction "XTAL2_12") (pintype "bidirectional"))
      (node (ref "Q6") (pin "1") (pinfunction "1_1") (pintype "passive"))
    )
    (net (code "59") (name "Net-(LED1-PadA)") (class "Default")
      (node (ref "LED1") (pin "A") (pinfunction "A_A") (pintype "passive"))
      (node (ref "R8") (pin "2") (pinfunction "2_2") (pintype "passive"))
    )
    (net (code "60") (name "Net-(LED2-PadA)") (class "Default")
      (node (ref "LED2") (pin "A") (pinfunction "A_A") (pintype "passive"))
      (node (ref "R9") (pin "2") (pinfunction "2_2") (pintype "passive"))
    )
    (net (code "61") (name "Net-(LED3-C)") (class "Default")
      (node (ref "LED3") (pin "K") (pinfunction "C_K") (pintype "passive"))
      (node (ref "OK1") (pin "1") (pinfunction "A_1") (pintype "passive"))
    )
    (net (code "62") (name "Net-(LED3-PadA)") (class "Default")
      (node (ref "LED3") (pin "A") (pinfunction "A_A") (pintype "passive"))
      (node (ref "R4") (pin "1") (pinfunction "1_1") (pintype "passive"))
    )
    (net (code "63") (name "Net-(LED4-C)") (class "Default")
      (node (ref "LED4") (pin "K") (pinfunction "C_K") (pintype "passive"))
      (node (ref "OK1") (pin "5") (pinfunction "A_5") (pintype "passive"))
    )
    (net (code "64") (name "Net-(LED4-PadA)") (class "Default")
      (node (ref "LED4") (pin "A") (pinfunction "A_A") (pintype "passive"))
      (node (ref "R12") (pin "1") (pinfunction "1_1") (pintype "passive"))
    )
    (net (code "65") (name "Net-(LED5-PadA)") (class "Default")
      (node (ref "LED5") (pin "A") (pinfunction "A_A") (pintype "passive"))
      (node (ref "R10") (pin "2") (pinfunction "2_2") (pintype "passive"))
    )
    (net (code "66") (name "Net-(LED6-C)") (class "Default")
      (node (ref "LED6") (pin "K") (pinfunction "C_K") (pintype "passive"))
      (node (ref "U2") (pin "23") (pinfunction "CBUS0_23") (pintype "bidirectional"))
    )
    (net (code "67") (name "Net-(LED6-PadA)") (class "Default")
      (node (ref "LED6") (pin "A") (pinfunction "A_A") (pintype "passive"))
      (node (ref "R11") (pin "1") (pinfunction "1_1") (pintype "passive"))
    )
    (net (code "68") (name "Net-(LED7-PadA)") (class "Default")
      (node (ref "LED7") (pin "A") (pinfunction "A_A") (pintype "passive"))
      (node (ref "R25") (pin "2") (pinfunction "2_2") (pintype "passive"))
    )
    (net (code "69") (name "Net-(LED8-PadA)") (class "Default")
      (node (ref "LED8") (pin "A") (pinfunction "A_A") (pintype "passive"))
      (node (ref "R26") (pin "2") (pinfunction "2_2") (pintype "passive"))
    )
    (net (code "70") (name "Net-(LED9-PadA)") (class "Default")
      (node (ref "LED9") (pin "A") (pinfunction "A_A") (pintype "passive"))
      (node (ref "R27") (pin "2") (pinfunction "2_2") (pintype "passive"))
    )
    (net (code "71") (name "Net-(LED10-PadA)") (class "Default")
      (node (ref "LED10") (pin "A") (pinfunction "A_A") (pintype "passive"))
      (node (ref "R2") (pin "1") (pinfunction "1_1") (pintype "passive"))
    )
    (net (code "72") (name "Net-(LED11-C)") (class "Default")
      (node (ref "LED11") (pin "K") (pinfunction "C_K") (pintype "passive"))
      (node (ref "OK2") (pin "1") (pinfunction "A_1") (pintype "passive"))
    )
    (net (code "73") (name "Net-(LED11-PadA)") (class "Default")
      (node (ref "LED11") (pin "A") (pinfunction "A_A") (pintype "passive"))
      (node (ref "R14") (pin "1") (pinfunction "1_1") (pintype "passive"))
    )
    (net (code "74") (name "Net-(LED12-PadA)") (class "Default")
      (node (ref "LED12") (pin "A") (pinfunction "A_A") (pintype "passive"))
      (node (ref "R34") (pin "1") (pinfunction "1_1") (pintype "passive"))
    )
    (net (code "75") (name "Net-(LED13-C)") (class "Default")
      (node (ref "LED13") (pin "K") (pinfunction "C_K") (pintype "passive"))
      (node (ref "U2") (pin "22") (pinfunction "CBUS1_22") (pintype "bidirectional"))
    )
    (net (code "76") (name "Net-(LED13-PadA)") (class "Default")
      (node (ref "LED13") (pin "A") (pinfunction "A_A") (pintype "passive"))
      (node (ref "R37") (pin "1") (pinfunction "1_1") (pintype "passive"))
    )
    (net (code "77") (name "Net-(LED14-PadA)") (class "Default")
      (node (ref "LED14") (pin "A") (pinfunction "A_A") (pintype "passive"))
      (node (ref "R3") (pin "1") (pinfunction "1_1") (pintype "passive"))
    )
    (net (code "78") (name "Net-(OK1A-COL)") (class "Default")
      (node (ref "OK1") (pin "16") (pinfunction "COL_16") (pintype "passive"))
      (node (ref "R18") (pin "2") (pinfunction "2_2") (pintype "passive"))
      (node (ref "STC102") (pin "1") (pinfunction "1_1") (pintype "passive"))
    )
    (net (code "79") (name "Net-(OK1B-A)") (class "Default")
      (node (ref "OK1") (pin "3") (pinfunction "A_3") (pintype "passive"))
      (node (ref "R5") (pin "1") (pinfunction "1_1") (pintype "passive"))
    )
    (net (code "80") (name "Net-(OK1B-COL)") (class "Default")
      (node (ref "OK1") (pin "14") (pinfunction "COL_14") (pintype "passive"))
      (node (ref "R19") (pin "2") (pinfunction "2_2") (pintype "passive"))
      (node (ref "STC102") (pin "3") (pinfunction "3_3") (pintype "passive"))
    )
    (net (code "81") (name "Net-(OK1C-COL)") (class "Default")
      (node (ref "OK1") (pin "12") (pinfunction "COL_12") (pintype "passive"))
      (node (ref "R20") (pin "2") (pinfunction "2_2") (pintype "passive"))
      (node (ref "STC102") (pin "5") (pinfunction "5_5") (pintype "passive"))
    )
    (net (code "82") (name "Net-(OK1D-A)") (class "Default")
      (node (ref "OK1") (pin "7") (pinfunction "A_7") (pintype "passive"))
      (node (ref "R13") (pin "1") (pinfunction "1_1") (pintype "passive"))
    )
    (net (code "83") (name "Net-(OK1D-COL)") (class "Default")
      (node (ref "OK1") (pin "10") (pinfunction "COL_10") (pintype "passive"))
      (node (ref "R21") (pin "2") (pinfunction "2_2") (pintype "passive"))
      (node (ref "STC102") (pin "7") (pinfunction "7_7") (pintype "passive"))
    )
    (net (code "84") (name "Net-(OK2A-COL)") (class "Default")
      (node (ref "OK2") (pin "16") (pinfunction "COL_16") (pintype "passive"))
      (node (ref "R22") (pin "2") (pinfunction "2_2") (pintype "passive"))
      (node (ref "STC102") (pin "9") (pinfunction "9_9") (pintype "passive"))
    )
    (net (code "85") (name "Net-(OK2B-A)") (class "Default")
      (node (ref "OK2") (pin "3") (pinfunction "A_3") (pintype "passive"))
      (node (ref "R15") (pin "1") (pinfunction "1_1") (pintype "passive"))
    )
    (net (code "86") (name "Net-(OK2B-COL)") (class "Default")
      (node (ref "OK2") (pin "14") (pinfunction "COL_14") (pintype "passive"))
      (node (ref "R23") (pin "2") (pinfunction "2_2") (pintype "passive"))
      (node (ref "STC102") (pin "11") (pinfunction "11_11") (pintype "passive"))
    )
    (net (code "87") (name "Net-(OK2C-A)") (class "Default")
      (node (ref "OK2") (pin "5") (pinfunction "A_5") (pintype "passive"))
      (node (ref "R16") (pin "1") (pinfunction "1_1") (pintype "passive"))
    )
    (net (code "88") (name "Net-(OK2D-A)") (class "Default")
      (node (ref "OK2") (pin "7") (pinfunction "A_7") (pintype "passive"))
      (node (ref "R45") (pin "1") (pinfunction "1_1") (pintype "passive"))
    )
    (net (code "89") (name "Net-(Q5-PadG)") (class "Default")
      (node (ref "Q5") (pin "G") (pinfunction "G_G") (pintype "passive"))
      (node (ref "R28") (pin "1") (pinfunction "1_1") (pintype "passive"))
    )
    (net (code "90") (name "Net-(U2-3V3OUT)") (class "Default")
      (node (ref "C7") (pin "2") (pinfunction "2_2") (pintype "passive"))
      (node (ref "U2") (pin "17") (pinfunction "3V3OUT_17") (pintype "output"))
    )
    (net (code "91") (name "unconnected-(IC5-(ADC4)PA4-Pad36)") (class "Default")
      (node (ref "IC5") (pin "36") (pinfunction "(ADC4)PA4_36") (pintype "bidirectional"))
    )
    (net (code "92") (name "unconnected-(IC5-(ADC5)PA5-Pad35)") (class "Default")
      (node (ref "IC5") (pin "35") (pinfunction "(ADC5)PA5_35") (pintype "bidirectional"))
    )
    (net (code "93") (name "unconnected-(IC5-(ADC6)PA6-Pad34)") (class "Default")
      (node (ref "IC5") (pin "34") (pinfunction "(ADC6)PA6_34") (pintype "bidirectional"))
    )
    (net (code "94") (name "unconnected-(IC5-(ADC7)PA7-Pad33)") (class "Default")
      (node (ref "IC5") (pin "33") (pinfunction "(ADC7)PA7_33") (pintype "bidirectional"))
    )
    (net (code "95") (name "unconnected-(PROGRAM-Pad3)") (class "Default")
      (node (ref "PROGRAM") (pin "3") (pinfunction "3_3") (pintype "passive"))
    )
    (net (code "96") (name "unconnected-(PROGRAM-Pad10)") (class "Default")
      (node (ref "PROGRAM") (pin "10") (pinfunction "10_10") (pintype "passive"))
    )
    (net (code "97") (name "unconnected-(STC102-Pad2)") (class "Default")
      (node (ref "STC102") (pin "2") (pinfunction "2_2") (pintype "passive"))
    )
    (net (code "98") (name "unconnected-(STC102-Pad12)") (class "Default")
      (node (ref "STC102") (pin "12") (pinfunction "12_12") (pintype "passive"))
    )
    (net (code "99") (name "unconnected-(STC102-Pad13)") (class "Default")
      (node (ref "STC102") (pin "13") (pinfunction "13_13") (pintype "passive"))
    )
    (net (code "100") (name "unconnected-(STC102-Pad14)") (class "Default")
      (node (ref "STC102") (pin "14") (pinfunction "14_14") (pintype "passive"))
    )
    (net (code "101") (name "unconnected-(STC102-Pad15)") (class "Default")
      (node (ref "STC102") (pin "15") (pinfunction "15_15") (pintype "passive"))
    )
    (net (code "102") (name "unconnected-(STC102-Pad16)") (class "Default")
      (node (ref "STC102") (pin "16") (pinfunction "16_16") (pintype "passive"))
    )
    (net (code "103") (name "unconnected-(U2-CBUS2-Pad13)") (class "Default")
      (node (ref "U2") (pin "13") (pinfunction "CBUS2_13") (pintype "bidirectional"))
    )
    (net (code "104") (name "unconnected-(U2-CBUS3-Pad14)") (class "Default")
      (node (ref "U2") (pin "14") (pinfunction "CBUS3_14") (pintype "bidirectional"))
    )
    (net (code "105") (name "unconnected-(U2-CBUS4-Pad12)") (class "Default")
      (node (ref "U2") (pin "12") (pinfunction "CBUS4_12") (pintype "bidirectional"))
    )
    (net (code "106") (name "unconnected-(U2-CTS#-Pad11)") (class "Default")
      (node (ref "U2") (pin "11") (pinfunction "CTS#_11") (pintype "input"))
    )
    (net (code "107") (name "unconnected-(U2-DCD#-Pad10)") (class "Default")
      (node (ref "U2") (pin "10") (pinfunction "DCD#_10") (pintype "input"))
    )
    (net (code "108") (name "unconnected-(U2-DSR#-Pad9)") (class "Default")
      (node (ref "U2") (pin "9") (pinfunction "DSR#_9") (pintype "input"))
    )
    (net (code "109") (name "unconnected-(U2-DTR#-Pad2)") (class "Default")
      (node (ref "U2") (pin "2") (pinfunction "DTR#_2") (pintype "output"))
    )
    (net (code "110") (name "unconnected-(U2-OSCI-Pad27)") (class "Default")
      (node (ref "U2") (pin "27") (pinfunction "OSCI_27") (pintype "input"))
    )
    (net (code "111") (name "unconnected-(U2-OSCO-Pad28)") (class "Default")
      (node (ref "U2") (pin "28") (pinfunction "OSCO_28") (pintype "output"))
    )
    (net (code "112") (name "unconnected-(U2-RI#-Pad6)") (class "Default")
      (node (ref "U2") (pin "6") (pinfunction "RI#_6") (pintype "input"))
    )
    (net (code "113") (name "unconnected-(U2-RTS#-Pad3)") (class "Default")
      (node (ref "U2") (pin "3") (pinfunction "RTS#_3") (pintype "output"))
    )
  )
)
